# primero.net
KiCad netlist of a schematic drawn in EAGLE
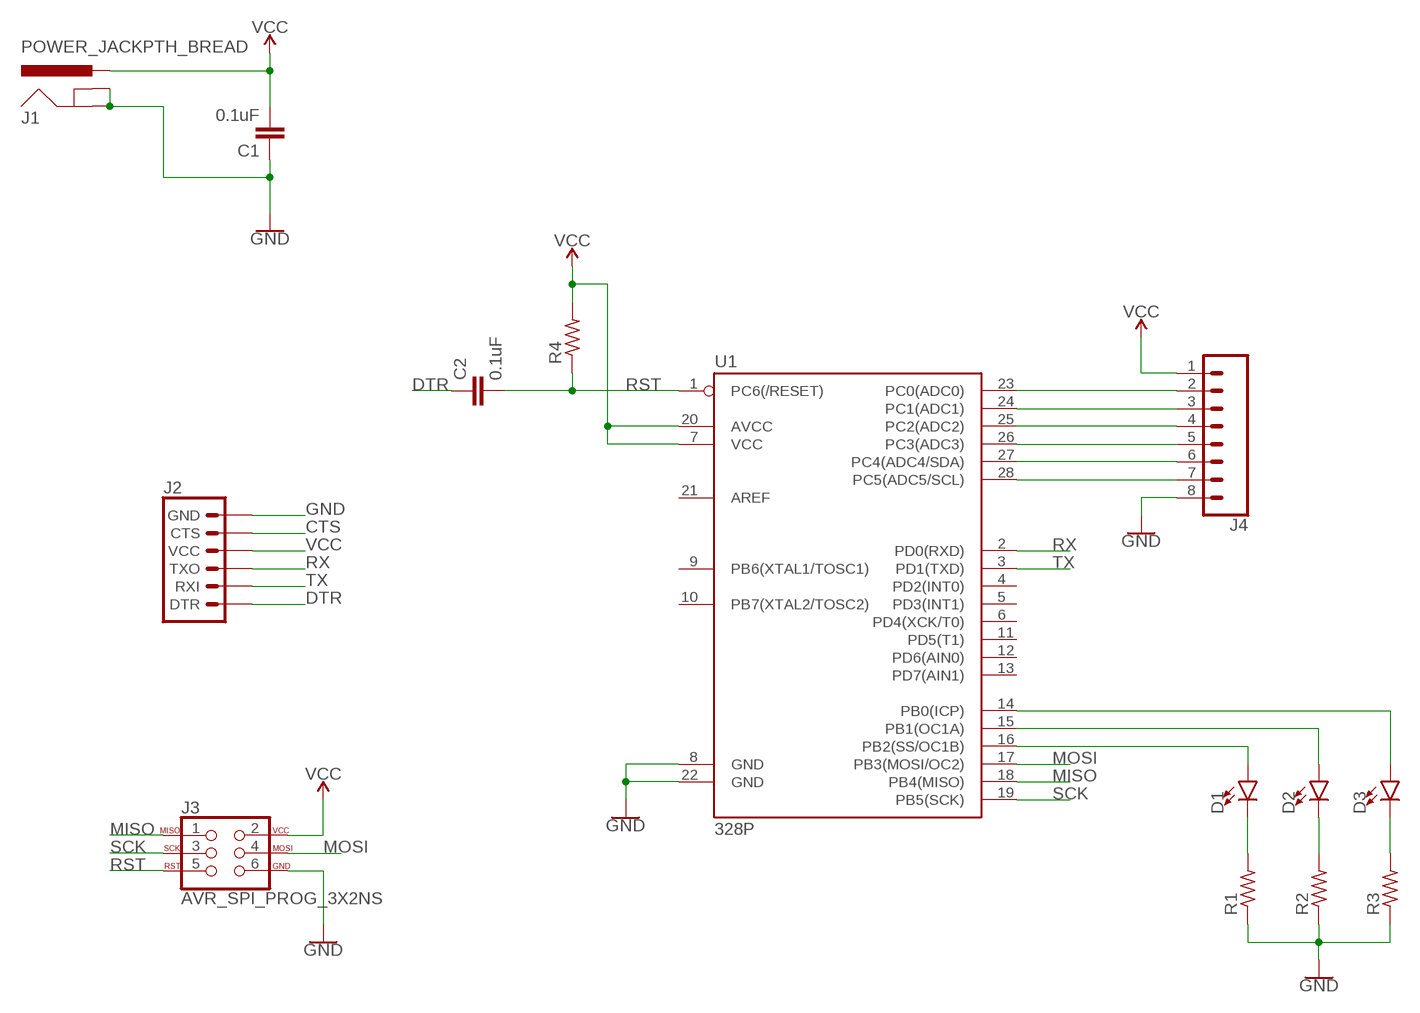
[diagram p0: schematic, sheet 1]

(export (version "E")
  (design (tool "Eeschema 10.0.6"))
  (components
    (comp (ref "C1")
      (value "0.1uF")
      (footprint "eagle-import:CAP-PTH-SMALL-KIT")
      (libsource (lib "eagle-import") (part "0.1UF-KIT-EZ-50V-20%"))
    )
    (comp (ref "C2")
      (value "0.1uF")
      (footprint "eagle-import:CAP-PTH-SMALL-KIT")
      (libsource (lib "eagle-import") (part "0.1UF-KIT-EZ-50V-20%"))
    )
    (comp (ref "D1")
      (value "LED5MM")
      (footprint "eagle-import:LED_5MM")
      (libsource (lib "eagle-import") (part "LED5MM"))
    )
    (comp (ref "D2")
      (value "LED5MM")
      (footprint "eagle-import:LED_5MM")
      (libsource (lib "eagle-import") (part "LED5MM"))
    )
    (comp (ref "D3")
      (value "LED5MM")
      (footprint "eagle-import:LED_5MM")
      (libsource (lib "eagle-import") (part "LED5MM"))
    )
    (comp (ref "J1")
      (value "POWER_JACKPTH_BREAD")
      (footprint "eagle-import:POWER_JACK_PTH_BREAD")
      (libsource (lib "eagle-import") (part "POWER_JACKPTH_BREAD"))
    )
    (comp (ref "J2")
      (value "6_PIN_SERIAL_TARGET")
      (footprint "eagle-import:1X06")
      (libsource (lib "eagle-import") (part "6_PIN_SERIAL_TARGET"))
    )
    (comp (ref "J3")
      (value "AVR_SPI_PROG_3X2NS")
      (footprint "eagle-import:2X3-NS")
      (libsource (lib "eagle-import") (part "AVR_SPI_PROG_3X2NS"))
    )
    (comp (ref "J4")
      (value "CONN_08\"")
      (footprint "eagle-import:1X08")
      (libsource (lib "eagle-import") (part "CONN_08{dblquote}"))
    )
    (comp (ref "R1")
      (value "R-US_0204/5")
      (footprint "eagle-import:0204_5")
      (libsource (lib "eagle-import") (part "R-US_0204/5"))
    )
    (comp (ref "R2")
      (value "R-US_0204/5")
      (footprint "eagle-import:0204_5")
      (libsource (lib "eagle-import") (part "R-US_0204/5"))
    )
    (comp (ref "R3")
      (value "R-US_0204/5")
      (footprint "eagle-import:0204_5")
      (libsource (lib "eagle-import") (part "R-US_0204/5"))
    )
    (comp (ref "R4")
      (value "R-US_0204/5")
      (footprint "eagle-import:0204_5")
      (libsource (lib "eagle-import") (part "R-US_0204/5"))
    )
    (comp (ref "U1")
      (value "328P")
      (footprint "eagle-import:DIP28")
      (libsource (lib "eagle-import") (part "ATMEGA328P_PDIP"))
    )
  )
  (nets
    (net (code "1") (name "/CTS") (class "Default")
      (node (ref "J2") (pin "5") (pinfunction "CTS_5") (pintype "passive"))
    )
    (net (code "2") (name "/DTR") (class "Default")
      (node (ref "C2") (pin "1") (pinfunction "1_1") (pintype "passive"))
      (node (ref "J2") (pin "1") (pinfunction "DTR_1") (pintype "passive"))
    )
    (net (code "3") (name "/MISO") (class "Default")
      (node (ref "J3") (pin "1") (pinfunction "1_1") (pintype "passive"))
      (node (ref "U1") (pin "18") (pinfunction "PB4(MISO)_18") (pintype "bidirectional"))
    )
    (net (code "4") (name "/MOSI") (class "Default")
      (node (ref "J3") (pin "4") (pinfunction "4_4") (pintype "passive"))
      (node (ref "U1") (pin "17") (pinfunction "PB3(MOSI/OC2)_17") (pintype "bidirectional"))
    )
    (net (code "5") (name "/RST") (class "Default")
      (node (ref "C2") (pin "2") (pinfunction "2_2") (pintype "passive"))
      (node (ref "J3") (pin "5") (pinfunction "5_5") (pintype "passive"))
      (node (ref "R4") (pin "1") (pinfunction "1_1") (pintype "passive"))
      (node (ref "U1") (pin "1") (pinfunction "PC6(/RESET)_1") (pintype "bidirectional"))
    )
    (net (code "6") (name "/RX") (class "Default")
      (node (ref "J2") (pin "3") (pinfunction "TXO_3") (pintype "passive"))
      (node (ref "U1") (pin "2") (pinfunction "PD0(RXD)_2") (pintype "bidirectional"))
    )
    (net (code "7") (name "/SCK") (class "Default")
      (node (ref "J3") (pin "3") (pinfunction "3_3") (pintype "passive"))
      (node (ref "U1") (pin "19") (pinfunction "PB5(SCK)_19") (pintype "bidirectional"))
    )
    (net (code "8") (name "/TX") (class "Default")
      (node (ref "J2") (pin "2") (pinfunction "RXI_2") (pintype "passive"))
      (node (ref "U1") (pin "3") (pinfunction "PD1(TXD)_3") (pintype "bidirectional"))
    )
    (net (code "9") (name "GND") (class "Default")
      (node (ref "C1") (pin "1") (pinfunction "1_1") (pintype "passive"))
      (node (ref "J1") (pin "GND") (pinfunction "GND_GND") (pintype "bidirectional"))
      (node (ref "J1") (pin "GNDBREAK") (pinfunction "GNDBREAK_GNDBREAK") (pintype "bidirectional"))
      (node (ref "J2") (pin "6") (pinfunction "GND_6") (pintype "passive"))
      (node (ref "J3") (pin "6") (pinfunction "6_6") (pintype "passive"))
      (node (ref "J4") (pin "8") (pinfunction "8_8") (pintype "passive"))
      (node (ref "R1") (pin "1") (pinfunction "1_1") (pintype "passive"))
      (node (ref "R2") (pin "1") (pinfunction "1_1") (pintype "passive"))
      (node (ref "R3") (pin "1") (pinfunction "1_1") (pintype "passive"))
      (node (ref "U1") (pin "22") (pinfunction "GND_22") (pintype "bidirectional"))
      (node (ref "U1") (pin "8") (pinfunction "GND_8") (pintype "bidirectional"))
    )
    (net (code "10") (name "Net-(D1-C)") (class "Default")
      (node (ref "D1") (pin "K") (pinfunction "C_K") (pintype "passive"))
      (node (ref "R1") (pin "2") (pinfunction "2_2") (pintype "passive"))
    )
    (net (code "11") (name "Net-(D2-C)") (class "Default")
      (node (ref "D2") (pin "K") (pinfunction "C_K") (pintype "passive"))
      (node (ref "R2") (pin "2") (pinfunction "2_2") (pintype "passive"))
    )
    (net (code "12") (name "Net-(D3-C)") (class "Default")
      (node (ref "D3") (pin "K") (pinfunction "C_K") (pintype "passive"))
      (node (ref "R3") (pin "2") (pinfunction "2_2") (pintype "passive"))
    )
    (net (code "13") (name "Net-(U1-PB0(ICP))") (class "Default")
      (node (ref "D3") (pin "A") (pinfunction "A_A") (pintype "passive"))
      (node (ref "U1") (pin "14") (pinfunction "PB0(ICP)_14") (pintype "bidirectional"))
    )
    (net (code "14") (name "Net-(U1-PB1(OC1A))") (class "Default")
      (node (ref "D2") (pin "A") (pinfunction "A_A") (pintype "passive"))
      (node (ref "U1") (pin "15") (pinfunction "PB1(OC1A)_15") (pintype "bidirectional"))
    )
    (net (code "15") (name "Net-(U1-PB2(SS{slash}OC1B))") (class "Default")
      (node (ref "D1") (pin "A") (pinfunction "A_A") (pintype "passive"))
      (node (ref "U1") (pin "16") (pinfunction "PB2(SS/OC1B)_16") (pintype "bidirectional"))
    )
    (net (code "16") (name "Net-(U1-PC0(ADC0))") (class "Default")
      (node (ref "J4") (pin "2") (pinfunction "2_2") (pintype "passive"))
      (node (ref "U1") (pin "23") (pinfunction "PC0(ADC0)_23") (pintype "bidirectional"))
    )
    (net (code "17") (name "Net-(U1-PC1(ADC1))") (class "Default")
      (node (ref "J4") (pin "3") (pinfunction "3_3") (pintype "passive"))
      (node (ref "U1") (pin "24") (pinfunction "PC1(ADC1)_24") (pintype "bidirectional"))
    )
    (net (code "18") (name "Net-(U1-PC2(ADC2))") (class "Default")
      (node (ref "J4") (pin "4") (pinfunction "4_4") (pintype "passive"))
      (node (ref "U1") (pin "25") (pinfunction "PC2(ADC2)_25") (pintype "bidirectional"))
    )
    (net (code "19") (name "Net-(U1-PC3(ADC3))") (class "Default")
      (node (ref "J4") (pin "5") (pinfunction "5_5") (pintype "passive"))
      (node (ref "U1") (pin "26") (pinfunction "PC3(ADC3)_26") (pintype "bidirectional"))
    )
    (net (code "20") (name "Net-(U1-PC4(ADC4{slash}SDA))") (class "Default")
      (node (ref "J4") (pin "6") (pinfunction "6_6") (pintype "passive"))
      (node (ref "U1") (pin "27") (pinfunction "PC4(ADC4/SDA)_27") (pintype "bidirectional"))
    )
    (net (code "21") (name "Net-(U1-PC5(ADC5{slash}SCL))") (class "Default")
      (node (ref "J4") (pin "7") (pinfunction "7_7") (pintype "passive"))
      (node (ref "U1") (pin "28") (pinfunction "PC5(ADC5/SCL)_28") (pintype "bidirectional"))
    )
    (net (code "22") (name "VCC") (class "Default")
      (node (ref "C1") (pin "2") (pinfunction "2_2") (pintype "passive"))
      (node (ref "J1") (pin "PWR") (pinfunction "PWR_PWR") (pintype "bidirectional"))
      (node (ref "J2") (pin "4") (pinfunction "VCC_4") (pintype "passive"))
      (node (ref "J3") (pin "2") (pinfunction "2_2") (pintype "passive"))
      (node (ref "J4") (pin "1") (pinfunction "1_1") (pintype "passive"))
      (node (ref "R4") (pin "2") (pinfunction "2_2") (pintype "passive"))
      (node (ref "U1") (pin "20") (pinfunction "AVCC_20") (pintype "bidirectional"))
      (node (ref "U1") (pin "7") (pinfunction "VCC_7") (pintype "bidirectional"))
    )
    (net (code "23") (name "unconnected-(U1-AREF-Pad21)") (class "Default")
      (node (ref "U1") (pin "21") (pinfunction "AREF_21") (pintype "bidirectional"))
    )
    (net (code "24") (name "unconnected-(U1-PB6(XTAL1{slash}TOSC1)-Pad9)") (class "Default")
      (node (ref "U1") (pin "9") (pinfunction "PB6(XTAL1/TOSC1)_9") (pintype "bidirectional"))
    )
    (net (code "25") (name "unconnected-(U1-PB7(XTAL2{slash}TOSC2)-Pad10)") (class "Default")
      (node (ref "U1") (pin "10") (pinfunction "PB7(XTAL2/TOSC2)_10") (pintype "bidirectional"))
    )
    (net (code "26") (name "unconnected-(U1-PD2(INT0)-Pad4)") (class "Default")
      (node (ref "U1") (pin "4") (pinfunction "PD2(INT0)_4") (pintype "bidirectional"))
    )
    (net (code "27") (name "unconnected-(U1-PD3(INT1)-Pad5)") (class "Default")
      (node (ref "U1") (pin "5") (pinfunction "PD3(INT1)_5") (pintype "bidirectional"))
    )
    (net (code "28") (name "unconnected-(U1-PD4(XCK{slash}T0)-Pad6)") (class "Default")
      (node (ref "U1") (pin "6") (pinfunction "PD4(XCK/T0)_6") (pintype "bidirectional"))
    )
    (net (code "29") (name "unconnected-(U1-PD5(T1)-Pad11)") (class "Default")
      (node (ref "U1") (pin "11") (pinfunction "PD5(T1)_11") (pintype "bidirectional"))
    )
    (net (code "30") (name "unconnected-(U1-PD6(AIN0)-Pad12)") (class "Default")
      (node (ref "U1") (pin "12") (pinfunction "PD6(AIN0)_12") (pintype "bidirectional"))
    )
    (net (code "31") (name "unconnected-(U1-PD7(AIN1)-Pad13)") (class "Default")
      (node (ref "U1") (pin "13") (pinfunction "PD7(AIN1)_13") (pintype "bidirectional"))
    )
  )
)
